# COBConnector.net
KiCad netlist of a schematic drawn in Altium Designer
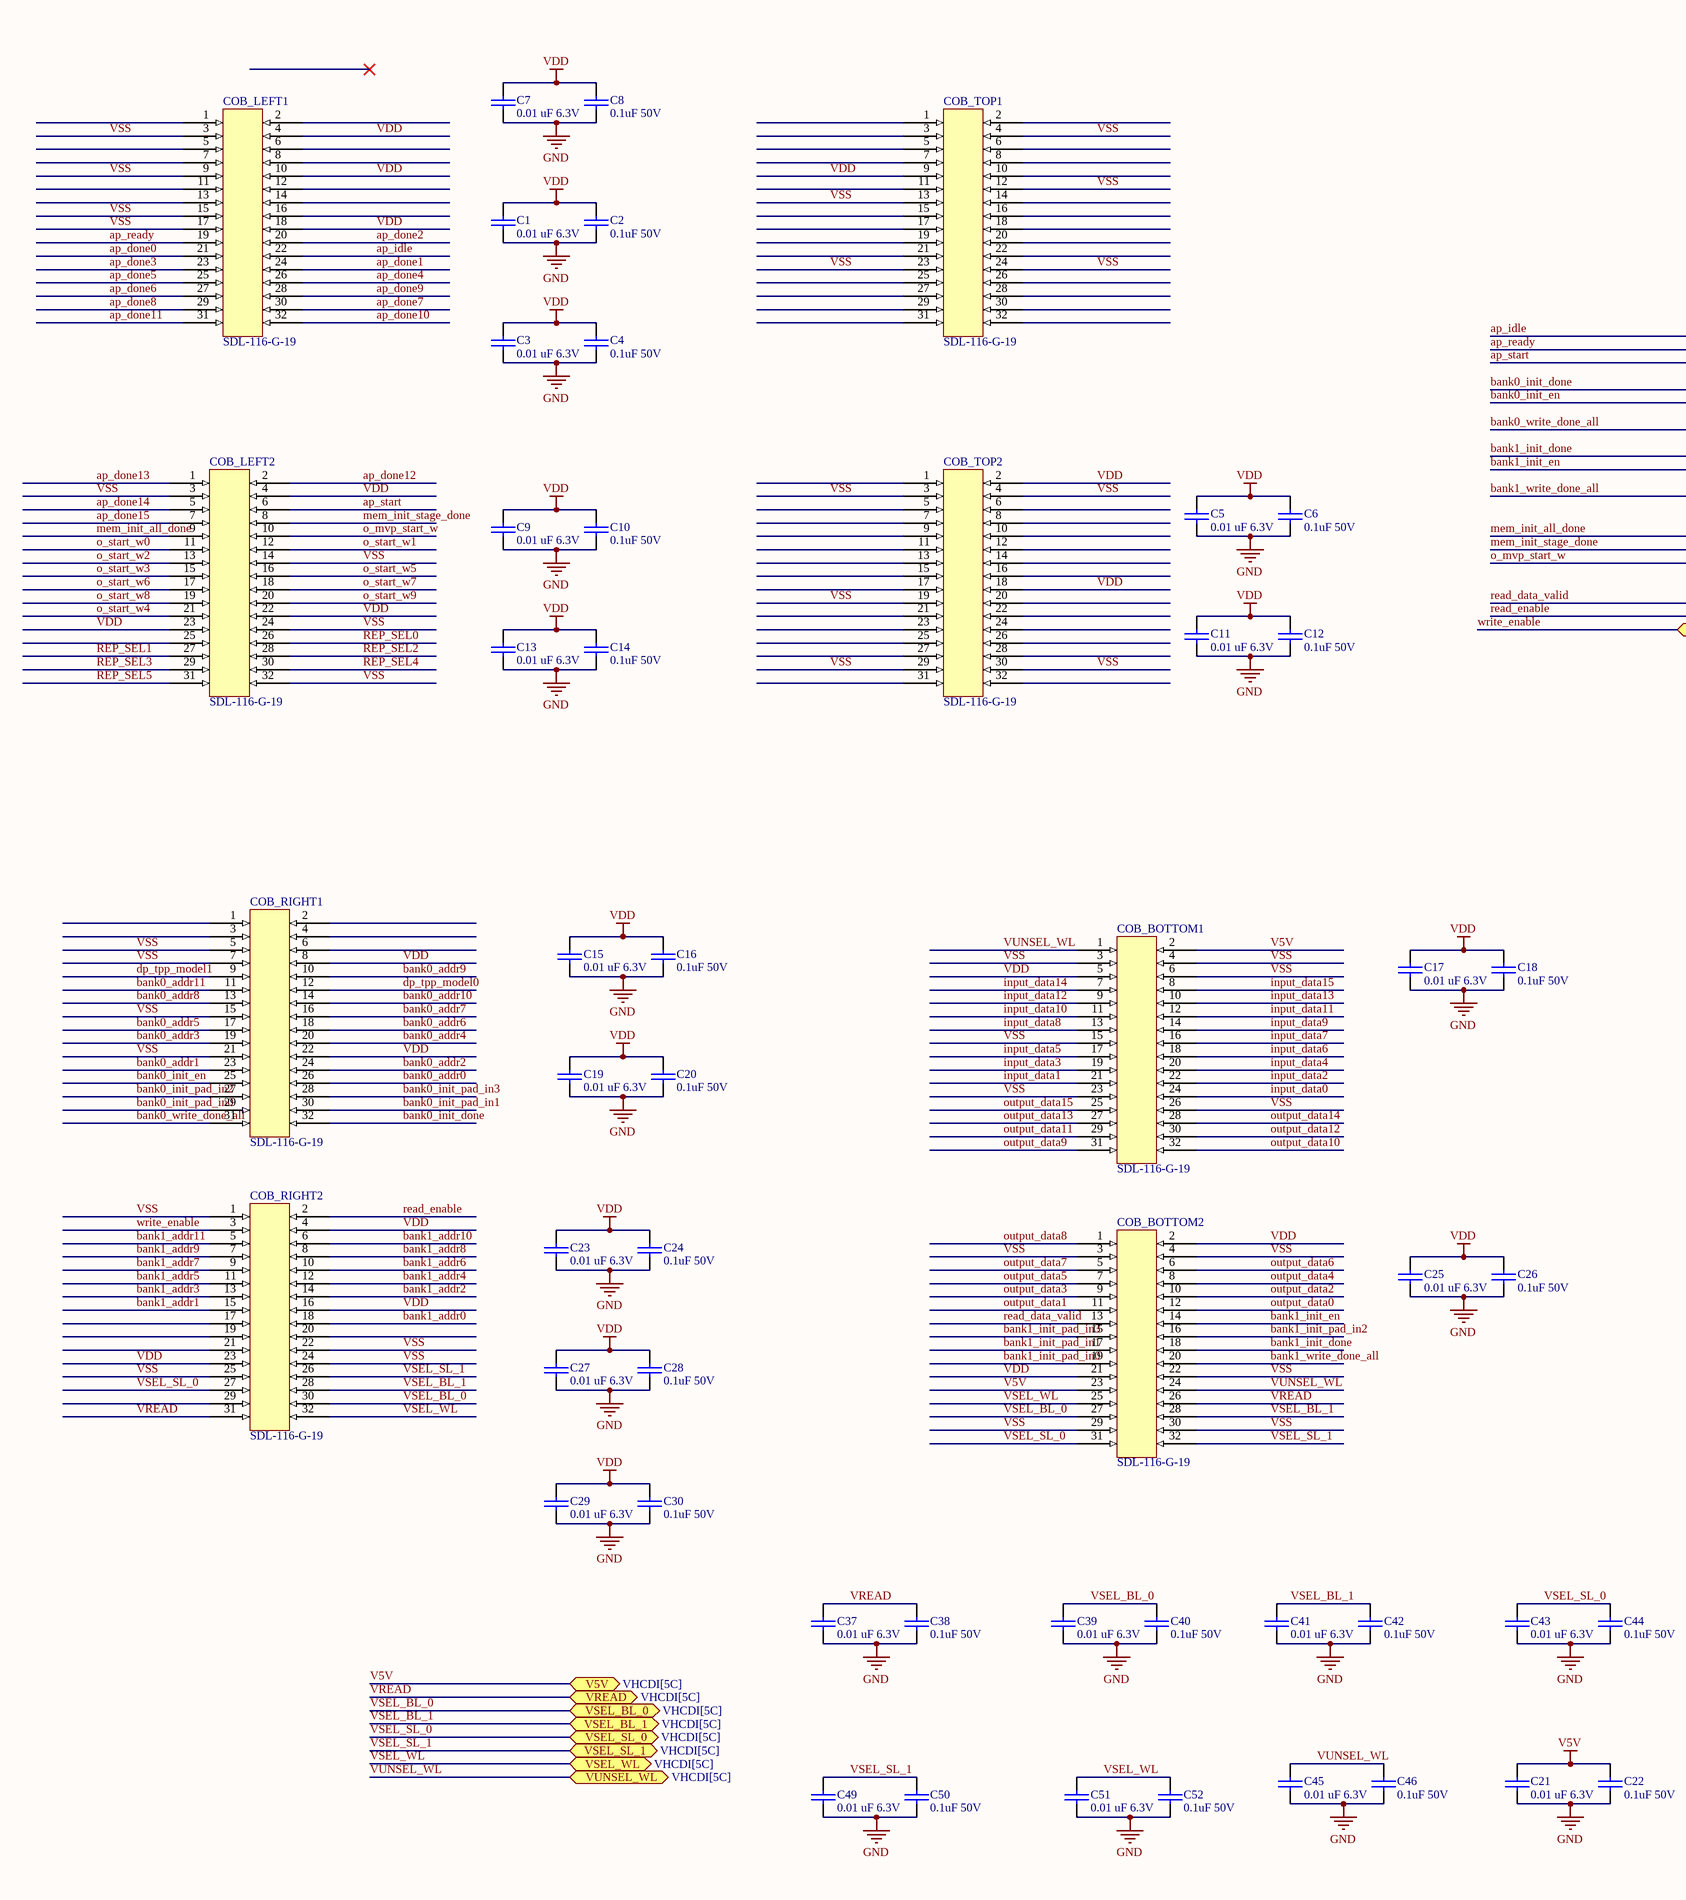
[diagram p0: COBConnector.SchDoc, left]
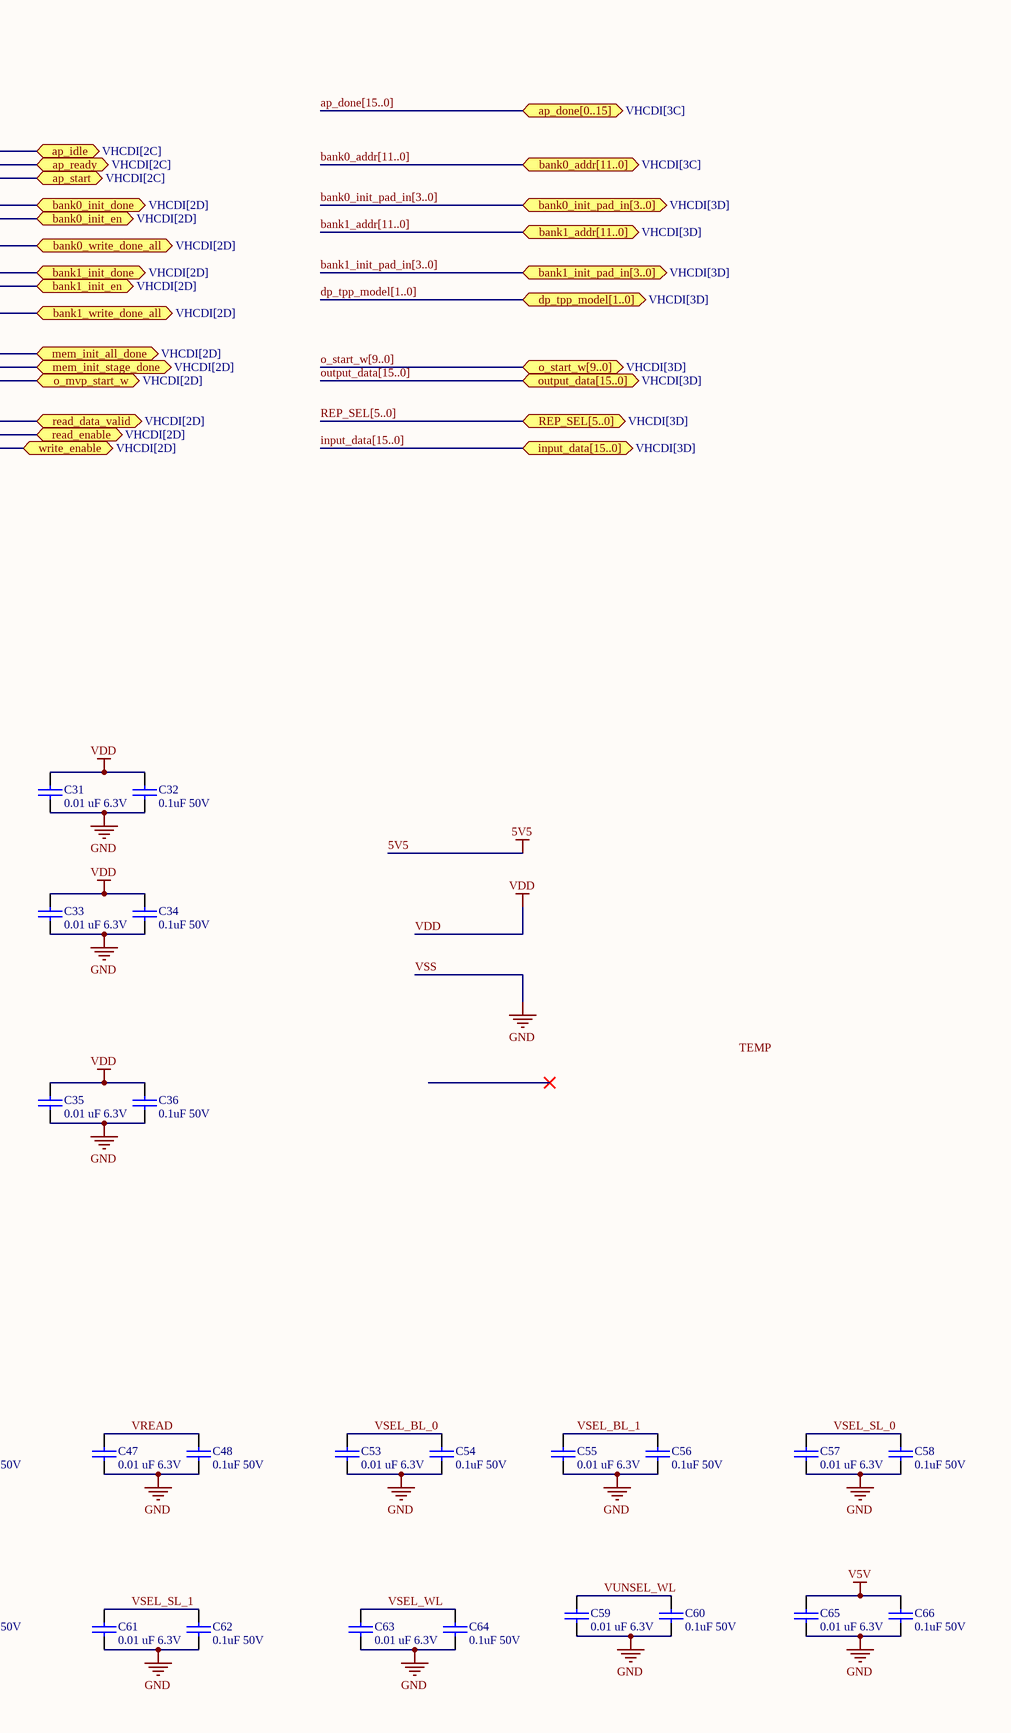
[diagram p1: COBConnector.SchDoc, right]

(export (version "E")
  (design (tool "Eeschema 10.0.6"))
  (components
    (comp (ref "C1")
      (value "0.01 uF 6.3V")
      (footprint "C0603-XXXXXX-XXX")
      (description "Multilayer Ceramic Capacitors MLCC - SMD/SMT 6.3V 0.01uF X7R 0603 20%")
      (libsource (lib "00-100001-001") (part "C0603F103M9RACTU"))
    )
    (comp (ref "C2")
      (value "0.1uF 50V")
      (footprint "C0603-XXXXXX-XXX")
      (description "0.1 µF ±20% 50V Ceramic Capacitor X7R 0603")
      (libsource (lib "00-100001-001") (part "C0603C104M5RAC7867"))
    )
    (comp (ref "C3")
      (value "0.01 uF 6.3V")
      (footprint "C0603-XXXXXX-XXX")
      (description "Multilayer Ceramic Capacitors MLCC - SMD/SMT 6.3V 0.01uF X7R 0603 20%")
      (libsource (lib "00-100001-001") (part "C0603F103M9RACTU"))
    )
    (comp (ref "C4")
      (value "0.1uF 50V")
      (footprint "C0603-XXXXXX-XXX")
      (description "0.1 µF ±20% 50V Ceramic Capacitor X7R 0603")
      (libsource (lib "00-100001-001") (part "C0603C104M5RAC7867"))
    )
    (comp (ref "C5")
      (value "0.01 uF 6.3V")
      (footprint "C0603-XXXXXX-XXX")
      (description "Multilayer Ceramic Capacitors MLCC - SMD/SMT 6.3V 0.01uF X7R 0603 20%")
      (libsource (lib "00-100001-001") (part "C0603F103M9RACTU"))
    )
    (comp (ref "C6")
      (value "0.1uF 50V")
      (footprint "C0603-XXXXXX-XXX")
      (description "0.1 µF ±20% 50V Ceramic Capacitor X7R 0603")
      (libsource (lib "00-100001-001") (part "C0603C104M5RAC7867"))
    )
    (comp (ref "C7")
      (value "0.01 uF 6.3V")
      (footprint "C0603-XXXXXX-XXX")
      (description "Multilayer Ceramic Capacitors MLCC - SMD/SMT 6.3V 0.01uF X7R 0603 20%")
      (libsource (lib "00-100001-001") (part "C0603F103M9RACTU"))
    )
    (comp (ref "C8")
      (value "0.1uF 50V")
      (footprint "C0603-XXXXXX-XXX")
      (description "0.1 µF ±20% 50V Ceramic Capacitor X7R 0603")
      (libsource (lib "00-100001-001") (part "C0603C104M5RAC7867"))
    )
    (comp (ref "C9")
      (value "0.01 uF 6.3V")
      (footprint "C0603-XXXXXX-XXX")
      (description "Multilayer Ceramic Capacitors MLCC - SMD/SMT 6.3V 0.01uF X7R 0603 20%")
      (libsource (lib "00-100001-001") (part "C0603F103M9RACTU"))
    )
    (comp (ref "C10")
      (value "0.1uF 50V")
      (footprint "C0603-XXXXXX-XXX")
      (description "0.1 µF ±20% 50V Ceramic Capacitor X7R 0603")
      (libsource (lib "00-100001-001") (part "C0603C104M5RAC7867"))
    )
    (comp (ref "C11")
      (value "0.01 uF 6.3V")
      (footprint "C0603-XXXXXX-XXX")
      (description "Multilayer Ceramic Capacitors MLCC - SMD/SMT 6.3V 0.01uF X7R 0603 20%")
      (libsource (lib "00-100001-001") (part "C0603F103M9RACTU"))
    )
    (comp (ref "C12")
      (value "0.1uF 50V")
      (footprint "C0603-XXXXXX-XXX")
      (description "0.1 µF ±20% 50V Ceramic Capacitor X7R 0603")
      (libsource (lib "00-100001-001") (part "C0603C104M5RAC7867"))
    )
    (comp (ref "C13")
      (value "0.01 uF 6.3V")
      (footprint "C0603-XXXXXX-XXX")
      (description "Multilayer Ceramic Capacitors MLCC - SMD/SMT 6.3V 0.01uF X7R 0603 20%")
      (libsource (lib "00-100001-001") (part "C0603F103M9RACTU"))
    )
    (comp (ref "C14")
      (value "0.1uF 50V")
      (footprint "C0603-XXXXXX-XXX")
      (description "0.1 µF ±20% 50V Ceramic Capacitor X7R 0603")
      (libsource (lib "00-100001-001") (part "C0603C104M5RAC7867"))
    )
    (comp (ref "C15")
      (value "0.01 uF 6.3V")
      (footprint "C0603-XXXXXX-XXX")
      (description "Multilayer Ceramic Capacitors MLCC - SMD/SMT 6.3V 0.01uF X7R 0603 20%")
      (libsource (lib "00-100001-001") (part "C0603F103M9RACTU"))
    )
    (comp (ref "C16")
      (value "0.1uF 50V")
      (footprint "C0603-XXXXXX-XXX")
      (description "0.1 µF ±20% 50V Ceramic Capacitor X7R 0603")
      (libsource (lib "00-100001-001") (part "C0603C104M5RAC7867"))
    )
    (comp (ref "C17")
      (value "0.01 uF 6.3V")
      (footprint "C0603-XXXXXX-XXX")
      (description "Multilayer Ceramic Capacitors MLCC - SMD/SMT 6.3V 0.01uF X7R 0603 20%")
      (libsource (lib "00-100001-001") (part "C0603F103M9RACTU"))
    )
    (comp (ref "C18")
      (value "0.1uF 50V")
      (footprint "C0603-XXXXXX-XXX")
      (description "0.1 µF ±20% 50V Ceramic Capacitor X7R 0603")
      (libsource (lib "00-100001-001") (part "C0603C104M5RAC7867"))
    )
    (comp (ref "C19")
      (value "0.01 uF 6.3V")
      (footprint "C0603-XXXXXX-XXX")
      (description "Multilayer Ceramic Capacitors MLCC - SMD/SMT 6.3V 0.01uF X7R 0603 20%")
      (libsource (lib "00-100001-001") (part "C0603F103M9RACTU"))
    )
    (comp (ref "C20")
      (value "0.1uF 50V")
      (footprint "C0603-XXXXXX-XXX")
      (description "0.1 µF ±20% 50V Ceramic Capacitor X7R 0603")
      (libsource (lib "00-100001-001") (part "C0603C104M5RAC7867"))
    )
    (comp (ref "C21")
      (value "0.01 uF 6.3V")
      (footprint "C0603-XXXXXX-XXX")
      (description "Multilayer Ceramic Capacitors MLCC - SMD/SMT 6.3V 0.01uF X7R 0603 20%")
      (libsource (lib "00-100001-001") (part "C0603F103M9RACTU"))
    )
    (comp (ref "C22")
      (value "0.1uF 50V")
      (footprint "C0603-XXXXXX-XXX")
      (description "0.1 µF ±20% 50V Ceramic Capacitor X7R 0603")
      (libsource (lib "00-100001-001") (part "C0603C104M5RAC7867"))
    )
    (comp (ref "C23")
      (value "0.01 uF 6.3V")
      (footprint "C0603-XXXXXX-XXX")
      (description "Multilayer Ceramic Capacitors MLCC - SMD/SMT 6.3V 0.01uF X7R 0603 20%")
      (libsource (lib "00-100001-001") (part "C0603F103M9RACTU"))
    )
    (comp (ref "C24")
      (value "0.1uF 50V")
      (footprint "C0603-XXXXXX-XXX")
      (description "0.1 µF ±20% 50V Ceramic Capacitor X7R 0603")
      (libsource (lib "00-100001-001") (part "C0603C104M5RAC7867"))
    )
    (comp (ref "C25")
      (value "0.01 uF 6.3V")
      (footprint "C0603-XXXXXX-XXX")
      (description "Multilayer Ceramic Capacitors MLCC - SMD/SMT 6.3V 0.01uF X7R 0603 20%")
      (libsource (lib "00-100001-001") (part "C0603F103M9RACTU"))
    )
    (comp (ref "C26")
      (value "0.1uF 50V")
      (footprint "C0603-XXXXXX-XXX")
      (description "0.1 µF ±20% 50V Ceramic Capacitor X7R 0603")
      (libsource (lib "00-100001-001") (part "C0603C104M5RAC7867"))
    )
    (comp (ref "C27")
      (value "0.01 uF 6.3V")
      (footprint "C0603-XXXXXX-XXX")
      (description "Multilayer Ceramic Capacitors MLCC - SMD/SMT 6.3V 0.01uF X7R 0603 20%")
      (libsource (lib "00-100001-001") (part "C0603F103M9RACTU"))
    )
    (comp (ref "C28")
      (value "0.1uF 50V")
      (footprint "C0603-XXXXXX-XXX")
      (description "0.1 µF ±20% 50V Ceramic Capacitor X7R 0603")
      (libsource (lib "00-100001-001") (part "C0603C104M5RAC7867"))
    )
    (comp (ref "C29")
      (value "0.01 uF 6.3V")
      (footprint "C0603-XXXXXX-XXX")
      (description "Multilayer Ceramic Capacitors MLCC - SMD/SMT 6.3V 0.01uF X7R 0603 20%")
      (libsource (lib "00-100001-001") (part "C0603F103M9RACTU"))
    )
    (comp (ref "C30")
      (value "0.1uF 50V")
      (footprint "C0603-XXXXXX-XXX")
      (description "0.1 µF ±20% 50V Ceramic Capacitor X7R 0603")
      (libsource (lib "00-100001-001") (part "C0603C104M5RAC7867"))
    )
    (comp (ref "C31")
      (value "0.01 uF 6.3V")
      (footprint "C0603-XXXXXX-XXX")
      (description "Multilayer Ceramic Capacitors MLCC - SMD/SMT 6.3V 0.01uF X7R 0603 20%")
      (libsource (lib "00-100001-001") (part "C0603F103M9RACTU"))
    )
    (comp (ref "C32")
      (value "0.1uF 50V")
      (footprint "C0603-XXXXXX-XXX")
      (description "0.1 µF ±20% 50V Ceramic Capacitor X7R 0603")
      (libsource (lib "00-100001-001") (part "C0603C104M5RAC7867"))
    )
    (comp (ref "C33")
      (value "0.01 uF 6.3V")
      (footprint "C0603-XXXXXX-XXX")
      (description "Multilayer Ceramic Capacitors MLCC - SMD/SMT 6.3V 0.01uF X7R 0603 20%")
      (libsource (lib "00-100001-001") (part "C0603F103M9RACTU"))
    )
    (comp (ref "C34")
      (value "0.1uF 50V")
      (footprint "C0603-XXXXXX-XXX")
      (description "0.1 µF ±20% 50V Ceramic Capacitor X7R 0603")
      (libsource (lib "00-100001-001") (part "C0603C104M5RAC7867"))
    )
    (comp (ref "C35")
      (value "0.01 uF 6.3V")
      (footprint "C0603-XXXXXX-XXX")
      (description "Multilayer Ceramic Capacitors MLCC - SMD/SMT 6.3V 0.01uF X7R 0603 20%")
      (libsource (lib "00-100001-001") (part "C0603F103M9RACTU"))
    )
    (comp (ref "C36")
      (value "0.1uF 50V")
      (footprint "C0603-XXXXXX-XXX")
      (description "0.1 µF ±20% 50V Ceramic Capacitor X7R 0603")
      (libsource (lib "00-100001-001") (part "C0603C104M5RAC7867"))
    )
    (comp (ref "C37")
      (value "0.01 uF 6.3V")
      (footprint "C0603-XXXXXX-XXX")
      (description "Multilayer Ceramic Capacitors MLCC - SMD/SMT 6.3V 0.01uF X7R 0603 20%")
      (libsource (lib "00-100001-001") (part "C0603F103M9RACTU"))
    )
    (comp (ref "C38")
      (value "0.1uF 50V")
      (footprint "C0603-XXXXXX-XXX")
      (description "0.1 µF ±20% 50V Ceramic Capacitor X7R 0603")
      (libsource (lib "00-100001-001") (part "C0603C104M5RAC7867"))
    )
    (comp (ref "C39")
      (value "0.01 uF 6.3V")
      (footprint "C0603-XXXXXX-XXX")
      (description "Multilayer Ceramic Capacitors MLCC - SMD/SMT 6.3V 0.01uF X7R 0603 20%")
      (libsource (lib "00-100001-001") (part "C0603F103M9RACTU"))
    )
    (comp (ref "C40")
      (value "0.1uF 50V")
      (footprint "C0603-XXXXXX-XXX")
      (description "0.1 µF ±20% 50V Ceramic Capacitor X7R 0603")
      (libsource (lib "00-100001-001") (part "C0603C104M5RAC7867"))
    )
    (comp (ref "C41")
      (value "0.01 uF 6.3V")
      (footprint "C0603-XXXXXX-XXX")
      (description "Multilayer Ceramic Capacitors MLCC - SMD/SMT 6.3V 0.01uF X7R 0603 20%")
      (libsource (lib "00-100001-001") (part "C0603F103M9RACTU"))
    )
    (comp (ref "C42")
      (value "0.1uF 50V")
      (footprint "C0603-XXXXXX-XXX")
      (description "0.1 µF ±20% 50V Ceramic Capacitor X7R 0603")
      (libsource (lib "00-100001-001") (part "C0603C104M5RAC7867"))
    )
    (comp (ref "C43")
      (value "0.01 uF 6.3V")
      (footprint "C0603-XXXXXX-XXX")
      (description "Multilayer Ceramic Capacitors MLCC - SMD/SMT 6.3V 0.01uF X7R 0603 20%")
      (libsource (lib "00-100001-001") (part "C0603F103M9RACTU"))
    )
    (comp (ref "C44")
      (value "0.1uF 50V")
      (footprint "C0603-XXXXXX-XXX")
      (description "0.1 µF ±20% 50V Ceramic Capacitor X7R 0603")
      (libsource (lib "00-100001-001") (part "C0603C104M5RAC7867"))
    )
    (comp (ref "C45")
      (value "0.01 uF 6.3V")
      (footprint "C0603-XXXXXX-XXX")
      (description "Multilayer Ceramic Capacitors MLCC - SMD/SMT 6.3V 0.01uF X7R 0603 20%")
      (libsource (lib "00-100001-001") (part "C0603F103M9RACTU"))
    )
    (comp (ref "C46")
      (value "0.1uF 50V")
      (footprint "C0603-XXXXXX-XXX")
      (description "0.1 µF ±20% 50V Ceramic Capacitor X7R 0603")
      (libsource (lib "00-100001-001") (part "C0603C104M5RAC7867"))
    )
    (comp (ref "C47")
      (value "0.01 uF 6.3V")
      (footprint "C0603-XXXXXX-XXX")
      (description "Multilayer Ceramic Capacitors MLCC - SMD/SMT 6.3V 0.01uF X7R 0603 20%")
      (libsource (lib "00-100001-001") (part "C0603F103M9RACTU"))
    )
    (comp (ref "C48")
      (value "0.1uF 50V")
      (footprint "C0603-XXXXXX-XXX")
      (description "0.1 µF ±20% 50V Ceramic Capacitor X7R 0603")
      (libsource (lib "00-100001-001") (part "C0603C104M5RAC7867"))
    )
    (comp (ref "C49")
      (value "0.01 uF 6.3V")
      (footprint "C0603-XXXXXX-XXX")
      (description "Multilayer Ceramic Capacitors MLCC - SMD/SMT 6.3V 0.01uF X7R 0603 20%")
      (libsource (lib "00-100001-001") (part "C0603F103M9RACTU"))
    )
    (comp (ref "C50")
      (value "0.1uF 50V")
      (footprint "C0603-XXXXXX-XXX")
      (description "0.1 µF ±20% 50V Ceramic Capacitor X7R 0603")
      (libsource (lib "00-100001-001") (part "C0603C104M5RAC7867"))
    )
    (comp (ref "C51")
      (value "0.01 uF 6.3V")
      (footprint "C0603-XXXXXX-XXX")
      (description "Multilayer Ceramic Capacitors MLCC - SMD/SMT 6.3V 0.01uF X7R 0603 20%")
      (libsource (lib "00-100001-001") (part "C0603F103M9RACTU"))
    )
    (comp (ref "C52")
      (value "0.1uF 50V")
      (footprint "C0603-XXXXXX-XXX")
      (description "0.1 µF ±20% 50V Ceramic Capacitor X7R 0603")
      (libsource (lib "00-100001-001") (part "C0603C104M5RAC7867"))
    )
    (comp (ref "C53")
      (value "0.01 uF 6.3V")
      (footprint "C0603-XXXXXX-XXX")
      (description "Multilayer Ceramic Capacitors MLCC - SMD/SMT 6.3V 0.01uF X7R 0603 20%")
      (libsource (lib "00-100001-001") (part "C0603F103M9RACTU"))
    )
    (comp (ref "C54")
      (value "0.1uF 50V")
      (footprint "C0603-XXXXXX-XXX")
      (description "0.1 µF ±20% 50V Ceramic Capacitor X7R 0603")
      (libsource (lib "00-100001-001") (part "C0603C104M5RAC7867"))
    )
    (comp (ref "C55")
      (value "0.01 uF 6.3V")
      (footprint "C0603-XXXXXX-XXX")
      (description "Multilayer Ceramic Capacitors MLCC - SMD/SMT 6.3V 0.01uF X7R 0603 20%")
      (libsource (lib "00-100001-001") (part "C0603F103M9RACTU"))
    )
    (comp (ref "C56")
      (value "0.1uF 50V")
      (footprint "C0603-XXXXXX-XXX")
      (description "0.1 µF ±20% 50V Ceramic Capacitor X7R 0603")
      (libsource (lib "00-100001-001") (part "C0603C104M5RAC7867"))
    )
    (comp (ref "C57")
      (value "0.01 uF 6.3V")
      (footprint "C0603-XXXXXX-XXX")
      (description "Multilayer Ceramic Capacitors MLCC - SMD/SMT 6.3V 0.01uF X7R 0603 20%")
      (libsource (lib "00-100001-001") (part "C0603F103M9RACTU"))
    )
    (comp (ref "C58")
      (value "0.1uF 50V")
      (footprint "C0603-XXXXXX-XXX")
      (description "0.1 µF ±20% 50V Ceramic Capacitor X7R 0603")
      (libsource (lib "00-100001-001") (part "C0603C104M5RAC7867"))
    )
    (comp (ref "C59")
      (value "0.01 uF 6.3V")
      (footprint "C0603-XXXXXX-XXX")
      (description "Multilayer Ceramic Capacitors MLCC - SMD/SMT 6.3V 0.01uF X7R 0603 20%")
      (libsource (lib "00-100001-001") (part "C0603F103M9RACTU"))
    )
    (comp (ref "C60")
      (value "0.1uF 50V")
      (footprint "C0603-XXXXXX-XXX")
      (description "0.1 µF ±20% 50V Ceramic Capacitor X7R 0603")
      (libsource (lib "00-100001-001") (part "C0603C104M5RAC7867"))
    )
    (comp (ref "C61")
      (value "0.01 uF 6.3V")
      (footprint "C0603-XXXXXX-XXX")
      (description "Multilayer Ceramic Capacitors MLCC - SMD/SMT 6.3V 0.01uF X7R 0603 20%")
      (libsource (lib "00-100001-001") (part "C0603F103M9RACTU"))
    )
    (comp (ref "C62")
      (value "0.1uF 50V")
      (footprint "C0603-XXXXXX-XXX")
      (description "0.1 µF ±20% 50V Ceramic Capacitor X7R 0603")
      (libsource (lib "00-100001-001") (part "C0603C104M5RAC7867"))
    )
    (comp (ref "C63")
      (value "0.01 uF 6.3V")
      (footprint "C0603-XXXXXX-XXX")
      (description "Multilayer Ceramic Capacitors MLCC - SMD/SMT 6.3V 0.01uF X7R 0603 20%")
      (libsource (lib "00-100001-001") (part "C0603F103M9RACTU"))
    )
    (comp (ref "C64")
      (value "0.1uF 50V")
      (footprint "C0603-XXXXXX-XXX")
      (description "0.1 µF ±20% 50V Ceramic Capacitor X7R 0603")
      (libsource (lib "00-100001-001") (part "C0603C104M5RAC7867"))
    )
    (comp (ref "C65")
      (value "0.01 uF 6.3V")
      (footprint "C0603-XXXXXX-XXX")
      (description "Multilayer Ceramic Capacitors MLCC - SMD/SMT 6.3V 0.01uF X7R 0603 20%")
      (libsource (lib "00-100001-001") (part "C0603F103M9RACTU"))
    )
    (comp (ref "C66")
      (value "0.1uF 50V")
      (footprint "C0603-XXXXXX-XXX")
      (description "0.1 µF ±20% 50V Ceramic Capacitor X7R 0603")
      (libsource (lib "00-100001-001") (part "C0603C104M5RAC7867"))
    )
    (comp (ref "COB_BOTTOM1")
      (value "SDL-116-G-19")
      (footprint "CON32_2X16_TU_DSL_SAI")
      (libsource (lib "00-100001-001") (part "SDL-116-G-19"))
    )
    (comp (ref "COB_BOTTOM2")
      (value "SDL-116-G-19")
      (footprint "CON32_2X16_TU_DSL_SAI")
      (libsource (lib "00-100001-001") (part "SDL-116-G-19"))
    )
    (comp (ref "COB_LEFT1")
      (value "SDL-116-G-19")
      (footprint "CON32_2X16_TU_DSL_SAI")
      (libsource (lib "00-100001-001") (part "SDL-116-G-19"))
    )
    (comp (ref "COB_LEFT2")
      (value "SDL-116-G-19")
      (footprint "CON32_2X16_TU_DSL_SAI")
      (libsource (lib "00-100001-001") (part "SDL-116-G-19"))
    )
    (comp (ref "COB_RIGHT1")
      (value "SDL-116-G-19")
      (footprint "CON32_2X16_TU_DSL_SAI")
      (libsource (lib "00-100001-001") (part "SDL-116-G-19"))
    )
    (comp (ref "COB_RIGHT2")
      (value "SDL-116-G-19")
      (footprint "CON32_2X16_TU_DSL_SAI")
      (libsource (lib "00-100001-001") (part "SDL-116-G-19"))
    )
    (comp (ref "COB_TOP1")
      (value "SDL-116-G-19")
      (footprint "CON32_2X16_TU_DSL_SAI")
      (libsource (lib "00-100001-001") (part "SDL-116-G-19"))
    )
    (comp (ref "COB_TOP2")
      (value "SDL-116-G-19")
      (footprint "CON32_2X16_TU_DSL_SAI")
      (libsource (lib "00-100001-001") (part "SDL-116-G-19"))
    )
  )
  (nets
    (net (code "1") (name "/REP_SEL0") (class "Default")
      (node (ref "COB_LEFT2") (pin "26") (pintype "input"))
    )
    (net (code "2") (name "/REP_SEL1") (class "Default")
      (node (ref "COB_LEFT2") (pin "27") (pintype "input"))
    )
    (net (code "3") (name "/REP_SEL2") (class "Default")
      (node (ref "COB_LEFT2") (pin "28") (pintype "input"))
    )
    (net (code "4") (name "/REP_SEL3") (class "Default")
      (node (ref "COB_LEFT2") (pin "29") (pintype "input"))
    )
    (net (code "5") (name "/REP_SEL4") (class "Default")
      (node (ref "COB_LEFT2") (pin "30") (pintype "input"))
    )
    (net (code "6") (name "/REP_SEL5") (class "Default")
      (node (ref "COB_LEFT2") (pin "31") (pintype "input"))
    )
    (net (code "9") (name "/VREAD") (class "Default")
      (node (ref "C37") (pin "1") (pinfunction "1_1") (pintype "passive"))
      (node (ref "C38") (pin "1") (pinfunction "1_1") (pintype "passive"))
      (node (ref "C47") (pin "1") (pinfunction "1_1") (pintype "passive"))
      (node (ref "C48") (pin "1") (pinfunction "1_1") (pintype "passive"))
      (node (ref "COB_BOTTOM2") (pin "26") (pintype "input"))
      (node (ref "COB_RIGHT2") (pin "31") (pintype "input"))
    )
    (net (code "10") (name "/VSEL_BL_0") (class "Default")
      (node (ref "C39") (pin "1") (pinfunction "1_1") (pintype "passive"))
      (node (ref "C40") (pin "1") (pinfunction "1_1") (pintype "passive"))
      (node (ref "C53") (pin "1") (pinfunction "1_1") (pintype "passive"))
      (node (ref "C54") (pin "1") (pinfunction "1_1") (pintype "passive"))
      (node (ref "COB_BOTTOM2") (pin "27") (pintype "input"))
      (node (ref "COB_RIGHT2") (pin "30") (pintype "input"))
    )
    (net (code "11") (name "/VSEL_BL_1") (class "Default")
      (node (ref "C41") (pin "1") (pinfunction "1_1") (pintype "passive"))
      (node (ref "C42") (pin "1") (pinfunction "1_1") (pintype "passive"))
      (node (ref "C55") (pin "1") (pinfunction "1_1") (pintype "passive"))
      (node (ref "C56") (pin "1") (pinfunction "1_1") (pintype "passive"))
      (node (ref "COB_BOTTOM2") (pin "28") (pintype "input"))
      (node (ref "COB_RIGHT2") (pin "28") (pintype "input"))
    )
    (net (code "12") (name "/VSEL_SL_0") (class "Default")
      (node (ref "C43") (pin "1") (pinfunction "1_1") (pintype "passive"))
      (node (ref "C44") (pin "1") (pinfunction "1_1") (pintype "passive"))
      (node (ref "C57") (pin "1") (pinfunction "1_1") (pintype "passive"))
      (node (ref "C58") (pin "1") (pinfunction "1_1") (pintype "passive"))
      (node (ref "COB_BOTTOM2") (pin "31") (pintype "input"))
      (node (ref "COB_RIGHT2") (pin "27") (pintype "input"))
    )
    (net (code "13") (name "/VSEL_SL_1") (class "Default")
      (node (ref "C49") (pin "1") (pinfunction "1_1") (pintype "passive"))
      (node (ref "C50") (pin "1") (pinfunction "1_1") (pintype "passive"))
      (node (ref "C61") (pin "1") (pinfunction "1_1") (pintype "passive"))
      (node (ref "C62") (pin "1") (pinfunction "1_1") (pintype "passive"))
      (node (ref "COB_BOTTOM2") (pin "32") (pintype "input"))
      (node (ref "COB_RIGHT2") (pin "26") (pintype "input"))
    )
    (net (code "14") (name "/VSEL_WL") (class "Default")
      (node (ref "C51") (pin "1") (pinfunction "1_1") (pintype "passive"))
      (node (ref "C52") (pin "1") (pinfunction "1_1") (pintype "passive"))
      (node (ref "C63") (pin "1") (pinfunction "1_1") (pintype "passive"))
      (node (ref "C64") (pin "1") (pinfunction "1_1") (pintype "passive"))
      (node (ref "COB_BOTTOM2") (pin "25") (pintype "input"))
      (node (ref "COB_RIGHT2") (pin "32") (pintype "input"))
    )
    (net (code "15") (name "/VUNSEL_WL") (class "Default")
      (node (ref "C45") (pin "1") (pinfunction "1_1") (pintype "passive"))
      (node (ref "C46") (pin "1") (pinfunction "1_1") (pintype "passive"))
      (node (ref "C59") (pin "1") (pinfunction "1_1") (pintype "passive"))
      (node (ref "C60") (pin "1") (pinfunction "1_1") (pintype "passive"))
      (node (ref "COB_BOTTOM1") (pin "1") (pintype "input"))
      (node (ref "COB_BOTTOM2") (pin "24") (pintype "input"))
    )
    (net (code "16") (name "/ap_done0") (class "Default")
      (node (ref "COB_LEFT1") (pin "21") (pintype "input"))
    )
    (net (code "17") (name "/ap_done1") (class "Default")
      (node (ref "COB_LEFT1") (pin "24") (pintype "input"))
    )
    (net (code "18") (name "/ap_done2") (class "Default")
      (node (ref "COB_LEFT1") (pin "20") (pintype "input"))
    )
    (net (code "19") (name "/ap_done3") (class "Default")
      (node (ref "COB_LEFT1") (pin "23") (pintype "input"))
    )
    (net (code "20") (name "/ap_done4") (class "Default")
      (node (ref "COB_LEFT1") (pin "26") (pintype "input"))
    )
    (net (code "21") (name "/ap_done5") (class "Default")
      (node (ref "COB_LEFT1") (pin "25") (pintype "input"))
    )
    (net (code "22") (name "/ap_done6") (class "Default")
      (node (ref "COB_LEFT1") (pin "27") (pintype "input"))
    )
    (net (code "23") (name "/ap_done7") (class "Default")
      (node (ref "COB_LEFT1") (pin "30") (pintype "input"))
    )
    (net (code "24") (name "/ap_done8") (class "Default")
      (node (ref "COB_LEFT1") (pin "29") (pintype "input"))
    )
    (net (code "25") (name "/ap_done9") (class "Default")
      (node (ref "COB_LEFT1") (pin "28") (pintype "input"))
    )
    (net (code "26") (name "/ap_done10") (class "Default")
      (node (ref "COB_LEFT1") (pin "32") (pintype "input"))
    )
    (net (code "27") (name "/ap_done11") (class "Default")
      (node (ref "COB_LEFT1") (pin "31") (pintype "input"))
    )
    (net (code "28") (name "/ap_done12") (class "Default")
      (node (ref "COB_LEFT2") (pin "2") (pintype "input"))
    )
    (net (code "29") (name "/ap_done13") (class "Default")
      (node (ref "COB_LEFT2") (pin "1") (pintype "input"))
    )
    (net (code "30") (name "/ap_done14") (class "Default")
      (node (ref "COB_LEFT2") (pin "5") (pintype "input"))
    )
    (net (code "31") (name "/ap_done15") (class "Default")
      (node (ref "COB_LEFT2") (pin "7") (pintype "input"))
    )
    (net (code "33") (name "/ap_idle") (class "Default")
      (node (ref "COB_LEFT1") (pin "22") (pintype "input"))
    )
    (net (code "34") (name "/ap_ready") (class "Default")
      (node (ref "COB_LEFT1") (pin "19") (pintype "input"))
    )
    (net (code "35") (name "/ap_start") (class "Default")
      (node (ref "COB_LEFT2") (pin "6") (pintype "input"))
    )
    (net (code "36") (name "/bank0_addr0") (class "Default")
      (node (ref "COB_RIGHT1") (pin "26") (pintype "input"))
    )
    (net (code "37") (name "/bank0_addr1") (class "Default")
      (node (ref "COB_RIGHT1") (pin "23") (pintype "input"))
    )
    (net (code "38") (name "/bank0_addr2") (class "Default")
      (node (ref "COB_RIGHT1") (pin "24") (pintype "input"))
    )
    (net (code "39") (name "/bank0_addr3") (class "Default")
      (node (ref "COB_RIGHT1") (pin "19") (pintype "input"))
    )
    (net (code "40") (name "/bank0_addr4") (class "Default")
      (node (ref "COB_RIGHT1") (pin "20") (pintype "input"))
    )
    (net (code "41") (name "/bank0_addr5") (class "Default")
      (node (ref "COB_RIGHT1") (pin "17") (pintype "input"))
    )
    (net (code "42") (name "/bank0_addr6") (class "Default")
      (node (ref "COB_RIGHT1") (pin "18") (pintype "input"))
    )
    (net (code "43") (name "/bank0_addr7") (class "Default")
      (node (ref "COB_RIGHT1") (pin "16") (pintype "input"))
    )
    (net (code "44") (name "/bank0_addr8") (class "Default")
      (node (ref "COB_RIGHT1") (pin "13") (pintype "input"))
    )
    (net (code "45") (name "/bank0_addr9") (class "Default")
      (node (ref "COB_RIGHT1") (pin "10") (pintype "input"))
    )
    (net (code "46") (name "/bank0_addr10") (class "Default")
      (node (ref "COB_RIGHT1") (pin "14") (pintype "input"))
    )
    (net (code "47") (name "/bank0_addr11") (class "Default")
      (node (ref "COB_RIGHT1") (pin "11") (pintype "input"))
    )
    (net (code "49") (name "/bank0_init_done") (class "Default")
      (node (ref "COB_RIGHT1") (pin "32") (pintype "input"))
    )
    (net (code "50") (name "/bank0_init_en") (class "Default")
      (node (ref "COB_RIGHT1") (pin "25") (pintype "input"))
    )
    (net (code "51") (name "/bank0_init_pad_in0") (class "Default")
      (node (ref "COB_RIGHT1") (pin "29") (pintype "input"))
    )
    (net (code "52") (name "/bank0_init_pad_in1") (class "Default")
      (node (ref "COB_RIGHT1") (pin "30") (pintype "input"))
    )
    (net (code "53") (name "/bank0_init_pad_in2") (class "Default")
      (node (ref "COB_RIGHT1") (pin "27") (pintype "input"))
    )
    (net (code "54") (name "/bank0_init_pad_in3") (class "Default")
      (node (ref "COB_RIGHT1") (pin "28") (pintype "input"))
    )
    (net (code "56") (name "/bank0_write_done_all") (class "Default")
      (node (ref "COB_RIGHT1") (pin "31") (pintype "input"))
    )
    (net (code "57") (name "/bank1_addr0") (class "Default")
      (node (ref "COB_RIGHT2") (pin "18") (pintype "input"))
    )
    (net (code "58") (name "/bank1_addr1") (class "Default")
      (node (ref "COB_RIGHT2") (pin "15") (pintype "input"))
    )
    (net (code "59") (name "/bank1_addr2") (class "Default")
      (node (ref "COB_RIGHT2") (pin "14") (pintype "input"))
    )
    (net (code "60") (name "/bank1_addr3") (class "Default")
      (node (ref "COB_RIGHT2") (pin "13") (pintype "input"))
    )
    (net (code "61") (name "/bank1_addr4") (class "Default")
      (node (ref "COB_RIGHT2") (pin "12") (pintype "input"))
    )
    (net (code "62") (name "/bank1_addr5") (class "Default")
      (node (ref "COB_RIGHT2") (pin "11") (pintype "input"))
    )
    (net (code "63") (name "/bank1_addr6") (class "Default")
      (node (ref "COB_RIGHT2") (pin "10") (pintype "input"))
    )
    (net (code "64") (name "/bank1_addr7") (class "Default")
      (node (ref "COB_RIGHT2") (pin "9") (pintype "input"))
    )
    (net (code "65") (name "/bank1_addr8") (class "Default")
      (node (ref "COB_RIGHT2") (pin "8") (pintype "input"))
    )
    (net (code "66") (name "/bank1_addr9") (class "Default")
      (node (ref "COB_RIGHT2") (pin "7") (pintype "input"))
    )
    (net (code "67") (name "/bank1_addr10") (class "Default")
      (node (ref "COB_RIGHT2") (pin "6") (pintype "input"))
    )
    (net (code "68") (name "/bank1_addr11") (class "Default")
      (node (ref "COB_RIGHT2") (pin "5") (pintype "input"))
    )
    (net (code "70") (name "/bank1_init_done") (class "Default")
      (node (ref "COB_BOTTOM2") (pin "18") (pintype "input"))
    )
    (net (code "71") (name "/bank1_init_en") (class "Default")
      (node (ref "COB_BOTTOM2") (pin "14") (pintype "input"))
    )
    (net (code "72") (name "/bank1_init_pad_in0") (class "Default")
      (node (ref "COB_BOTTOM2") (pin "19") (pintype "input"))
    )
    (net (code "73") (name "/bank1_init_pad_in1") (class "Default")
      (node (ref "COB_BOTTOM2") (pin "17") (pintype "input"))
    )
    (net (code "74") (name "/bank1_init_pad_in2") (class "Default")
      (node (ref "COB_BOTTOM2") (pin "16") (pintype "input"))
    )
    (net (code "75") (name "/bank1_init_pad_in3") (class "Default")
      (node (ref "COB_BOTTOM2") (pin "15") (pintype "input"))
    )
    (net (code "77") (name "/bank1_write_done_all") (class "Default")
      (node (ref "COB_BOTTOM2") (pin "20") (pintype "input"))
    )
    (net (code "78") (name "/dp_tpp_model0") (class "Default")
      (node (ref "COB_RIGHT1") (pin "12") (pintype "input"))
    )
    (net (code "79") (name "/dp_tpp_model1") (class "Default")
      (node (ref "COB_RIGHT1") (pin "9") (pintype "input"))
    )
    (net (code "81") (name "/input_data0") (class "Default")
      (node (ref "COB_BOTTOM1") (pin "24") (pintype "input"))
    )
    (net (code "82") (name "/input_data1") (class "Default")
      (node (ref "COB_BOTTOM1") (pin "21") (pintype "input"))
    )
    (net (code "83") (name "/input_data2") (class "Default")
      (node (ref "COB_BOTTOM1") (pin "22") (pintype "input"))
    )
    (net (code "84") (name "/input_data3") (class "Default")
      (node (ref "COB_BOTTOM1") (pin "19") (pintype "input"))
    )
    (net (code "85") (name "/input_data4") (class "Default")
      (node (ref "COB_BOTTOM1") (pin "20") (pintype "input"))
    )
    (net (code "86") (name "/input_data5") (class "Default")
      (node (ref "COB_BOTTOM1") (pin "17") (pintype "input"))
    )
    (net (code "87") (name "/input_data6") (class "Default")
      (node (ref "COB_BOTTOM1") (pin "18") (pintype "input"))
    )
    (net (code "88") (name "/input_data7") (class "Default")
      (node (ref "COB_BOTTOM1") (pin "16") (pintype "input"))
    )
    (net (code "89") (name "/input_data8") (class "Default")
      (node (ref "COB_BOTTOM1") (pin "13") (pintype "input"))
    )
    (net (code "90") (name "/input_data9") (class "Default")
      (node (ref "COB_BOTTOM1") (pin "14") (pintype "input"))
    )
    (net (code "91") (name "/input_data10") (class "Default")
      (node (ref "COB_BOTTOM1") (pin "11") (pintype "input"))
    )
    (net (code "92") (name "/input_data11") (class "Default")
      (node (ref "COB_BOTTOM1") (pin "12") (pintype "input"))
    )
    (net (code "93") (name "/input_data12") (class "Default")
      (node (ref "COB_BOTTOM1") (pin "9") (pintype "input"))
    )
    (net (code "94") (name "/input_data13") (class "Default")
      (node (ref "COB_BOTTOM1") (pin "10") (pintype "input"))
    )
    (net (code "95") (name "/input_data14") (class "Default")
      (node (ref "COB_BOTTOM1") (pin "7") (pintype "input"))
    )
    (net (code "96") (name "/input_data15") (class "Default")
      (node (ref "COB_BOTTOM1") (pin "8") (pintype "input"))
    )
    (net (code "98") (name "/mem_init_all_done") (class "Default")
      (node (ref "COB_LEFT2") (pin "9") (pintype "input"))
    )
    (net (code "99") (name "/mem_init_stage_done") (class "Default")
      (node (ref "COB_LEFT2") (pin "8") (pintype "input"))
    )
    (net (code "100") (name "/o_mvp_start_w") (class "Default")
      (node (ref "COB_LEFT2") (pin "10") (pintype "input"))
    )
    (net (code "101") (name "/o_start_w0") (class "Default")
      (node (ref "COB_LEFT2") (pin "11") (pintype "input"))
    )
    (net (code "102") (name "/o_start_w1") (class "Default")
      (node (ref "COB_LEFT2") (pin "12") (pintype "input"))
    )
    (net (code "103") (name "/o_start_w2") (class "Default")
      (node (ref "COB_LEFT2") (pin "13") (pintype "input"))
    )
    (net (code "104") (name "/o_start_w3") (class "Default")
      (node (ref "COB_LEFT2") (pin "15") (pintype "input"))
    )
    (net (code "105") (name "/o_start_w4") (class "Default")
      (node (ref "COB_LEFT2") (pin "21") (pintype "input"))
    )
    (net (code "106") (name "/o_start_w5") (class "Default")
      (node (ref "COB_LEFT2") (pin "16") (pintype "input"))
    )
    (net (code "107") (name "/o_start_w6") (class "Default")
      (node (ref "COB_LEFT2") (pin "17") (pintype "input"))
    )
    (net (code "108") (name "/o_start_w7") (class "Default")
      (node (ref "COB_LEFT2") (pin "18") (pintype "input"))
    )
    (net (code "109") (name "/o_start_w8") (class "Default")
      (node (ref "COB_LEFT2") (pin "19") (pintype "input"))
    )
    (net (code "110") (name "/o_start_w9") (class "Default")
      (node (ref "COB_LEFT2") (pin "20") (pintype "input"))
    )
    (net (code "112") (name "/output_data0") (class "Default")
      (node (ref "COB_BOTTOM2") (pin "12") (pintype "input"))
    )
    (net (code "113") (name "/output_data1") (class "Default")
      (node (ref "COB_BOTTOM2") (pin "11") (pintype "input"))
    )
    (net (code "114") (name "/output_data2") (class "Default")
      (node (ref "COB_BOTTOM2") (pin "10") (pintype "input"))
    )
    (net (code "115") (name "/output_data3") (class "Default")
      (node (ref "COB_BOTTOM2") (pin "9") (pintype "input"))
    )
    (net (code "116") (name "/output_data4") (class "Default")
      (node (ref "COB_BOTTOM2") (pin "8") (pintype "input"))
    )
    (net (code "117") (name "/output_data5") (class "Default")
      (node (ref "COB_BOTTOM2") (pin "7") (pintype "input"))
    )
    (net (code "118") (name "/output_data6") (class "Default")
      (node (ref "COB_BOTTOM2") (pin "6") (pintype "input"))
    )
    (net (code "119") (name "/output_data7") (class "Default")
      (node (ref "COB_BOTTOM2") (pin "5") (pintype "input"))
    )
    (net (code "120") (name "/output_data8") (class "Default")
      (node (ref "COB_BOTTOM2") (pin "1") (pintype "input"))
    )
    (net (code "121") (name "/output_data9") (class "Default")
      (node (ref "COB_BOTTOM1") (pin "31") (pintype "input"))
    )
    (net (code "122") (name "/output_data10") (class "Default")
      (node (ref "COB_BOTTOM1") (pin "32") (pintype "input"))
    )
    (net (code "123") (name "/output_data11") (class "Default")
      (node (ref "COB_BOTTOM1") (pin "29") (pintype "input"))
    )
    (net (code "124") (name "/output_data12") (class "Default")
      (node (ref "COB_BOTTOM1") (pin "30") (pintype "input"))
    )
    (net (code "125") (name "/output_data13") (class "Default")
      (node (ref "COB_BOTTOM1") (pin "27") (pintype "input"))
    )
    (net (code "126") (name "/output_data14") (class "Default")
      (node (ref "COB_BOTTOM1") (pin "28") (pintype "input"))
    )
    (net (code "127") (name "/output_data15") (class "Default")
      (node (ref "COB_BOTTOM1") (pin "25") (pintype "input"))
    )
    (net (code "129") (name "/read_data_valid") (class "Default")
      (node (ref "COB_BOTTOM2") (pin "13") (pintype "input"))
    )
    (net (code "130") (name "/read_enable") (class "Default")
      (node (ref "COB_RIGHT2") (pin "2") (pintype "input"))
    )
    (net (code "131") (name "/write_enable") (class "Default")
      (node (ref "COB_RIGHT2") (pin "3") (pintype "input"))
    )
    (net (code "133") (name "GND") (class "Default")
      (node (ref "C1") (pin "2") (pinfunction "2_2") (pintype "passive"))
      (node (ref "C10") (pin "2") (pinfunction "2_2") (pintype "passive"))
      (node (ref "C11") (pin "2") (pinfunction "2_2") (pintype "passive"))
      (node (ref "C12") (pin "2") (pinfunction "2_2") (pintype "passive"))
      (node (ref "C13") (pin "2") (pinfunction "2_2") (pintype "passive"))
      (node (ref "C14") (pin "2") (pinfunction "2_2") (pintype "passive"))
      (node (ref "C15") (pin "2") (pinfunction "2_2") (pintype "passive"))
      (node (ref "C16") (pin "2") (pinfunction "2_2") (pintype "passive"))
      (node (ref "C17") (pin "2") (pinfunction "2_2") (pintype "passive"))
      (node (ref "C18") (pin "2") (pinfunction "2_2") (pintype "passive"))
      (node (ref "C19") (pin "2") (pinfunction "2_2") (pintype "passive"))
      (node (ref "C2") (pin "2") (pinfunction "2_2") (pintype "passive"))
      (node (ref "C20") (pin "2") (pinfunction "2_2") (pintype "passive"))
      (node (ref "C21") (pin "2") (pinfunction "2_2") (pintype "passive"))
      (node (ref "C22") (pin "2") (pinfunction "2_2") (pintype "passive"))
      (node (ref "C23") (pin "2") (pinfunction "2_2") (pintype "passive"))
      (node (ref "C24") (pin "2") (pinfunction "2_2") (pintype "passive"))
      (node (ref "C25") (pin "2") (pinfunction "2_2") (pintype "passive"))
      (node (ref "C26") (pin "2") (pinfunction "2_2") (pintype "passive"))
      (node (ref "C27") (pin "2") (pinfunction "2_2") (pintype "passive"))
      (node (ref "C28") (pin "2") (pinfunction "2_2") (pintype "passive"))
      (node (ref "C29") (pin "2") (pinfunction "2_2") (pintype "passive"))
      (node (ref "C3") (pin "2") (pinfunction "2_2") (pintype "passive"))
      (node (ref "C30") (pin "2") (pinfunction "2_2") (pintype "passive"))
      (node (ref "C31") (pin "2") (pinfunction "2_2") (pintype "passive"))
      (node (ref "C32") (pin "2") (pinfunction "2_2") (pintype "passive"))
      (node (ref "C33") (pin "2") (pinfunction "2_2") (pintype "passive"))
      (node (ref "C34") (pin "2") (pinfunction "2_2") (pintype "passive"))
      (node (ref "C35") (pin "2") (pinfunction "2_2") (pintype "passive"))
      (node (ref "C36") (pin "2") (pinfunction "2_2") (pintype "passive"))
      (node (ref "C37") (pin "2") (pinfunction "2_2") (pintype "passive"))
      (node (ref "C38") (pin "2") (pinfunction "2_2") (pintype "passive"))
      (node (ref "C39") (pin "2") (pinfunction "2_2") (pintype "passive"))
      (node (ref "C4") (pin "2") (pinfunction "2_2") (pintype "passive"))
      (node (ref "C40") (pin "2") (pinfunction "2_2") (pintype "passive"))
      (node (ref "C41") (pin "2") (pinfunction "2_2") (pintype "passive"))
      (node (ref "C42") (pin "2") (pinfunction "2_2") (pintype "passive"))
      (node (ref "C43") (pin "2") (pinfunction "2_2") (pintype "passive"))
      (node (ref "C44") (pin "2") (pinfunction "2_2") (pintype "passive"))
      (node (ref "C45") (pin "2") (pinfunction "2_2") (pintype "passive"))
      (node (ref "C46") (pin "2") (pinfunction "2_2") (pintype "passive"))
      (node (ref "C47") (pin "2") (pinfunction "2_2") (pintype "passive"))
      (node (ref "C48") (pin "2") (pinfunction "2_2") (pintype "passive"))
      (node (ref "C49") (pin "2") (pinfunction "2_2") (pintype "passive"))
      (node (ref "C5") (pin "2") (pinfunction "2_2") (pintype "passive"))
      (node (ref "C50") (pin "2") (pinfunction "2_2") (pintype "passive"))
      (node (ref "C51") (pin "2") (pinfunction "2_2") (pintype "passive"))
      (node (ref "C52") (pin "2") (pinfunction "2_2") (pintype "passive"))
      (node (ref "C53") (pin "2") (pinfunction "2_2") (pintype "passive"))
      (node (ref "C54") (pin "2") (pinfunction "2_2") (pintype "passive"))
      (node (ref "C55") (pin "2") (pinfunction "2_2") (pintype "passive"))
      (node (ref "C56") (pin "2") (pinfunction "2_2") (pintype "passive"))
      (node (ref "C57") (pin "2") (pinfunction "2_2") (pintype "passive"))
      (node (ref "C58") (pin "2") (pinfunction "2_2") (pintype "passive"))
      (node (ref "C59") (pin "2") (pinfunction "2_2") (pintype "passive"))
      (node (ref "C6") (pin "2") (pinfunction "2_2") (pintype "passive"))
      (node (ref "C60") (pin "2") (pinfunction "2_2") (pintype "passive"))
      (node (ref "C61") (pin "2") (pinfunction "2_2") (pintype "passive"))
      (node (ref "C62") (pin "2") (pinfunction "2_2") (pintype "passive"))
      (node (ref "C63") (pin "2") (pinfunction "2_2") (pintype "passive"))
      (node (ref "C64") (pin "2") (pinfunction "2_2") (pintype "passive"))
      (node (ref "C65") (pin "2") (pinfunction "2_2") (pintype "passive"))
      (node (ref "C66") (pin "2") (pinfunction "2_2") (pintype "passive"))
      (node (ref "C7") (pin "2") (pinfunction "2_2") (pintype "passive"))
      (node (ref "C8") (pin "2") (pinfunction "2_2") (pintype "passive"))
      (node (ref "C9") (pin "2") (pinfunction "2_2") (pintype "passive"))
      (node (ref "COB_BOTTOM1") (pin "15") (pintype "input"))
      (node (ref "COB_BOTTOM1") (pin "23") (pintype "input"))
      (node (ref "COB_BOTTOM1") (pin "26") (pintype "input"))
      (node (ref "COB_BOTTOM1") (pin "3") (pintype "input"))
      (node (ref "COB_BOTTOM1") (pin "4") (pintype "input"))
      (node (ref "COB_BOTTOM1") (pin "6") (pintype "input"))
      (node (ref "COB_BOTTOM2") (pin "22") (pintype "input"))
      (node (ref "COB_BOTTOM2") (pin "29") (pintype "input"))
      (node (ref "COB_BOTTOM2") (pin "3") (pintype "input"))
      (node (ref "COB_BOTTOM2") (pin "30") (pintype "input"))
      (node (ref "COB_BOTTOM2") (pin "4") (pintype "input"))
      (node (ref "COB_LEFT1") (pin "15") (pintype "input"))
      (node (ref "COB_LEFT1") (pin "17") (pintype "input"))
      (node (ref "COB_LEFT1") (pin "3") (pintype "input"))
      (node (ref "COB_LEFT1") (pin "9") (pintype "input"))
      (node (ref "COB_LEFT2") (pin "14") (pintype "input"))
      (node (ref "COB_LEFT2") (pin "24") (pintype "input"))
      (node (ref "COB_LEFT2") (pin "3") (pintype "input"))
      (node (ref "COB_LEFT2") (pin "32") (pintype "input"))
      (node (ref "COB_RIGHT1") (pin "15") (pintype "input"))
      (node (ref "COB_RIGHT1") (pin "21") (pintype "input"))
      (node (ref "COB_RIGHT1") (pin "5") (pintype "input"))
      (node (ref "COB_RIGHT1") (pin "7") (pintype "input"))
      (node (ref "COB_RIGHT2") (pin "1") (pintype "input"))
      (node (ref "COB_RIGHT2") (pin "22") (pintype "input"))
      (node (ref "COB_RIGHT2") (pin "24") (pintype "input"))
      (node (ref "COB_RIGHT2") (pin "25") (pintype "input"))
      (node (ref "COB_TOP1") (pin "12") (pintype "input"))
      (node (ref "COB_TOP1") (pin "13") (pintype "input"))
      (node (ref "COB_TOP1") (pin "23") (pintype "input"))
      (node (ref "COB_TOP1") (pin "24") (pintype "input"))
      (node (ref "COB_TOP1") (pin "4") (pintype "input"))
      (node (ref "COB_TOP2") (pin "19") (pintype "input"))
      (node (ref "COB_TOP2") (pin "29") (pintype "input"))
      (node (ref "COB_TOP2") (pin "3") (pintype "input"))
      (node (ref "COB_TOP2") (pin "30") (pintype "input"))
      (node (ref "COB_TOP2") (pin "4") (pintype "input"))
    )
    (net (code "134") (name "V5V") (class "Default")
      (node (ref "C21") (pin "1") (pinfunction "1_1") (pintype "passive"))
      (node (ref "C22") (pin "1") (pinfunction "1_1") (pintype "passive"))
      (node (ref "C65") (pin "1") (pinfunction "1_1") (pintype "passive"))
      (node (ref "C66") (pin "1") (pinfunction "1_1") (pintype "passive"))
      (node (ref "COB_BOTTOM1") (pin "2") (pintype "input"))
      (node (ref "COB_BOTTOM2") (pin "23") (pintype "input"))
    )
    (net (code "135") (name "VDD") (class "Default")
      (node (ref "C1") (pin "1") (pinfunction "1_1") (pintype "passive"))
      (node (ref "C10") (pin "1") (pinfunction "1_1") (pintype "passive"))
      (node (ref "C11") (pin "1") (pinfunction "1_1") (pintype "passive"))
      (node (ref "C12") (pin "1") (pinfunction "1_1") (pintype "passive"))
      (node (ref "C13") (pin "1") (pinfunction "1_1") (pintype "passive"))
      (node (ref "C14") (pin "1") (pinfunction "1_1") (pintype "passive"))
      (node (ref "C15") (pin "1") (pinfunction "1_1") (pintype "passive"))
      (node (ref "C16") (pin "1") (pinfunction "1_1") (pintype "passive"))
      (node (ref "C17") (pin "1") (pinfunction "1_1") (pintype "passive"))
      (node (ref "C18") (pin "1") (pinfunction "1_1") (pintype "passive"))
      (node (ref "C19") (pin "1") (pinfunction "1_1") (pintype "passive"))
      (node (ref "C2") (pin "1") (pinfunction "1_1") (pintype "passive"))
      (node (ref "C20") (pin "1") (pinfunction "1_1") (pintype "passive"))
      (node (ref "C23") (pin "1") (pinfunction "1_1") (pintype "passive"))
      (node (ref "C24") (pin "1") (pinfunction "1_1") (pintype "passive"))
      (node (ref "C25") (pin "1") (pinfunction "1_1") (pintype "passive"))
      (node (ref "C26") (pin "1") (pinfunction "1_1") (pintype "passive"))
      (node (ref "C27") (pin "1") (pinfunction "1_1") (pintype "passive"))
      (node (ref "C28") (pin "1") (pinfunction "1_1") (pintype "passive"))
      (node (ref "C29") (pin "1") (pinfunction "1_1") (pintype "passive"))
      (node (ref "C3") (pin "1") (pinfunction "1_1") (pintype "passive"))
      (node (ref "C30") (pin "1") (pinfunction "1_1") (pintype "passive"))
      (node (ref "C31") (pin "1") (pinfunction "1_1") (pintype "passive"))
      (node (ref "C32") (pin "1") (pinfunction "1_1") (pintype "passive"))
      (node (ref "C33") (pin "1") (pinfunction "1_1") (pintype "passive"))
      (node (ref "C34") (pin "1") (pinfunction "1_1") (pintype "passive"))
      (node (ref "C35") (pin "1") (pinfunction "1_1") (pintype "passive"))
      (node (ref "C36") (pin "1") (pinfunction "1_1") (pintype "passive"))
      (node (ref "C4") (pin "1") (pinfunction "1_1") (pintype "passive"))
      (node (ref "C5") (pin "1") (pinfunction "1_1") (pintype "passive"))
      (node (ref "C6") (pin "1") (pinfunction "1_1") (pintype "passive"))
      (node (ref "C7") (pin "1") (pinfunction "1_1") (pintype "passive"))
      (node (ref "C8") (pin "1") (pinfunction "1_1") (pintype "passive"))
      (node (ref "C9") (pin "1") (pinfunction "1_1") (pintype "passive"))
      (node (ref "COB_BOTTOM1") (pin "5") (pintype "input"))
      (node (ref "COB_BOTTOM2") (pin "2") (pintype "input"))
      (node (ref "COB_BOTTOM2") (pin "21") (pintype "input"))
      (node (ref "COB_LEFT1") (pin "10") (pintype "input"))
      (node (ref "COB_LEFT1") (pin "18") (pintype "input"))
      (node (ref "COB_LEFT1") (pin "4") (pintype "input"))
      (node (ref "COB_LEFT2") (pin "22") (pintype "input"))
      (node (ref "COB_LEFT2") (pin "23") (pintype "input"))
      (node (ref "COB_LEFT2") (pin "4") (pintype "input"))
      (node (ref "COB_RIGHT1") (pin "22") (pintype "input"))
      (node (ref "COB_RIGHT1") (pin "8") (pintype "input"))
      (node (ref "COB_RIGHT2") (pin "16") (pintype "input"))
      (node (ref "COB_RIGHT2") (pin "23") (pintype "input"))
      (node (ref "COB_RIGHT2") (pin "4") (pintype "input"))
      (node (ref "COB_TOP1") (pin "9") (pintype "input"))
      (node (ref "COB_TOP2") (pin "18") (pintype "input"))
      (node (ref "COB_TOP2") (pin "2") (pintype "input"))
    )
    (net (code "136") (name "unconnected-(COB_LEFT1-Pad1)") (class "Default")
      (node (ref "COB_LEFT1") (pin "1") (pintype "input"))
    )
    (net (code "137") (name "unconnected-(COB_LEFT1-Pad2)") (class "Default")
      (node (ref "COB_LEFT1") (pin "2") (pintype "input"))
    )
    (net (code "138") (name "unconnected-(COB_LEFT1-Pad5)") (class "Default")
      (node (ref "COB_LEFT1") (pin "5") (pintype "input"))
    )
    (net (code "139") (name "unconnected-(COB_LEFT1-Pad6)") (class "Default")
      (node (ref "COB_LEFT1") (pin "6") (pintype "input"))
    )
    (net (code "140") (name "unconnected-(COB_LEFT1-Pad7)") (class "Default")
      (node (ref "COB_LEFT1") (pin "7") (pintype "input"))
    )
    (net (code "141") (name "unconnected-(COB_LEFT1-Pad8)") (class "Default")
      (node (ref "COB_LEFT1") (pin "8") (pintype "input"))
    )
    (net (code "142") (name "unconnected-(COB_LEFT1-Pad11)") (class "Default")
      (node (ref "COB_LEFT1") (pin "11") (pintype "input"))
    )
    (net (code "143") (name "unconnected-(COB_LEFT1-Pad12)") (class "Default")
      (node (ref "COB_LEFT1") (pin "12") (pintype "input"))
    )
    (net (code "144") (name "unconnected-(COB_LEFT1-Pad13)") (class "Default")
      (node (ref "COB_LEFT1") (pin "13") (pintype "input"))
    )
    (net (code "145") (name "unconnected-(COB_LEFT1-Pad14)") (class "Default")
      (node (ref "COB_LEFT1") (pin "14") (pintype "input"))
    )
    (net (code "146") (name "unconnected-(COB_LEFT1-Pad16)") (class "Default")
      (node (ref "COB_LEFT1") (pin "16") (pintype "input"))
    )
    (net (code "147") (name "unconnected-(COB_LEFT2-Pad25)") (class "Default")
      (node (ref "COB_LEFT2") (pin "25") (pintype "input"))
    )
    (net (code "148") (name "unconnected-(COB_RIGHT1-Pad1)") (class "Default")
      (node (ref "COB_RIGHT1") (pin "1") (pintype "input"))
    )
    (net (code "149") (name "unconnected-(COB_RIGHT1-Pad2)") (class "Default")
      (node (ref "COB_RIGHT1") (pin "2") (pintype "input"))
    )
    (net (code "150") (name "unconnected-(COB_RIGHT1-Pad3)") (class "Default")
      (node (ref "COB_RIGHT1") (pin "3") (pintype "input"))
    )
    (net (code "151") (name "unconnected-(COB_RIGHT1-Pad4)") (class "Default")
      (node (ref "COB_RIGHT1") (pin "4") (pintype "input"))
    )
    (net (code "152") (name "unconnected-(COB_RIGHT1-Pad6)") (class "Default")
      (node (ref "COB_RIGHT1") (pin "6") (pintype "input"))
    )
    (net (code "153") (name "unconnected-(COB_RIGHT2-Pad17)") (class "Default")
      (node (ref "COB_RIGHT2") (pin "17") (pintype "input"))
    )
    (net (code "154") (name "unconnected-(COB_RIGHT2-Pad19)") (class "Default")
      (node (ref "COB_RIGHT2") (pin "19") (pintype "input"))
    )
    (net (code "155") (name "unconnected-(COB_RIGHT2-Pad20)") (class "Default")
      (node (ref "COB_RIGHT2") (pin "20") (pintype "input"))
    )
    (net (code "156") (name "unconnected-(COB_RIGHT2-Pad21)") (class "Default")
      (node (ref "COB_RIGHT2") (pin "21") (pintype "input"))
    )
    (net (code "157") (name "unconnected-(COB_RIGHT2-Pad29)") (class "Default")
      (node (ref "COB_RIGHT2") (pin "29") (pintype "input"))
    )
    (net (code "158") (name "unconnected-(COB_TOP1-Pad1)") (class "Default")
      (node (ref "COB_TOP1") (pin "1") (pintype "input"))
    )
    (net (code "159") (name "unconnected-(COB_TOP1-Pad2)") (class "Default")
      (node (ref "COB_TOP1") (pin "2") (pintype "input"))
    )
    (net (code "160") (name "unconnected-(COB_TOP1-Pad3)") (class "Default")
      (node (ref "COB_TOP1") (pin "3") (pintype "input"))
    )
    (net (code "161") (name "unconnected-(COB_TOP1-Pad5)") (class "Default")
      (node (ref "COB_TOP1") (pin "5") (pintype "input"))
    )
    (net (code "162") (name "unconnected-(COB_TOP1-Pad6)") (class "Default")
      (node (ref "COB_TOP1") (pin "6") (pintype "input"))
    )
    (net (code "163") (name "unconnected-(COB_TOP1-Pad7)") (class "Default")
      (node (ref "COB_TOP1") (pin "7") (pintype "input"))
    )
    (net (code "164") (name "unconnected-(COB_TOP1-Pad8)") (class "Default")
      (node (ref "COB_TOP1") (pin "8") (pintype "input"))
    )
    (net (code "165") (name "unconnected-(COB_TOP1-Pad10)") (class "Default")
      (node (ref "COB_TOP1") (pin "10") (pintype "input"))
    )
    (net (code "166") (name "unconnected-(COB_TOP1-Pad11)") (class "Default")
      (node (ref "COB_TOP1") (pin "11") (pintype "input"))
    )
    (net (code "167") (name "unconnected-(COB_TOP1-Pad14)") (class "Default")
      (node (ref "COB_TOP1") (pin "14") (pintype "input"))
    )
    (net (code "168") (name "unconnected-(COB_TOP1-Pad15)") (class "Default")
      (node (ref "COB_TOP1") (pin "15") (pintype "input"))
    )
    (net (code "169") (name "unconnected-(COB_TOP1-Pad16)") (class "Default")
      (node (ref "COB_TOP1") (pin "16") (pintype "input"))
    )
    (net (code "170") (name "unconnected-(COB_TOP1-Pad17)") (class "Default")
      (node (ref "COB_TOP1") (pin "17") (pintype "input"))
    )
    (net (code "171") (name "unconnected-(COB_TOP1-Pad18)") (class "Default")
      (node (ref "COB_TOP1") (pin "18") (pintype "input"))
    )
    (net (code "172") (name "unconnected-(COB_TOP1-Pad19)") (class "Default")
      (node (ref "COB_TOP1") (pin "19") (pintype "input"))
    )
    (net (code "173") (name "unconnected-(COB_TOP1-Pad20)") (class "Default")
      (node (ref "COB_TOP1") (pin "20") (pintype "input"))
    )
    (net (code "174") (name "unconnected-(COB_TOP1-Pad21)") (class "Default")
      (node (ref "COB_TOP1") (pin "21") (pintype "input"))
    )
    (net (code "175") (name "unconnected-(COB_TOP1-Pad22)") (class "Default")
      (node (ref "COB_TOP1") (pin "22") (pintype "input"))
    )
    (net (code "176") (name "unconnected-(COB_TOP1-Pad25)") (class "Default")
      (node (ref "COB_TOP1") (pin "25") (pintype "input"))
    )
    (net (code "177") (name "unconnected-(COB_TOP1-Pad26)") (class "Default")
      (node (ref "COB_TOP1") (pin "26") (pintype "input"))
    )
    (net (code "178") (name "unconnected-(COB_TOP1-Pad27)") (class "Default")
      (node (ref "COB_TOP1") (pin "27") (pintype "input"))
    )
    (net (code "179") (name "unconnected-(COB_TOP1-Pad28)") (class "Default")
      (node (ref "COB_TOP1") (pin "28") (pintype "input"))
    )
    (net (code "180") (name "unconnected-(COB_TOP1-Pad29)") (class "Default")
      (node (ref "COB_TOP1") (pin "29") (pintype "input"))
    )
    (net (code "181") (name "unconnected-(COB_TOP1-Pad30)") (class "Default")
      (node (ref "COB_TOP1") (pin "30") (pintype "input"))
    )
    (net (code "182") (name "unconnected-(COB_TOP1-Pad31)") (class "Default")
      (node (ref "COB_TOP1") (pin "31") (pintype "input"))
    )
    (net (code "183") (name "unconnected-(COB_TOP1-Pad32)") (class "Default")
      (node (ref "COB_TOP1") (pin "32") (pintype "input"))
    )
    (net (code "184") (name "unconnected-(COB_TOP2-Pad1)") (class "Default")
      (node (ref "COB_TOP2") (pin "1") (pintype "input"))
    )
    (net (code "185") (name "unconnected-(COB_TOP2-Pad5)") (class "Default")
      (node (ref "COB_TOP2") (pin "5") (pintype "input"))
    )
    (net (code "186") (name "unconnected-(COB_TOP2-Pad6)") (class "Default")
      (node (ref "COB_TOP2") (pin "6") (pintype "input"))
    )
    (net (code "187") (name "unconnected-(COB_TOP2-Pad7)") (class "Default")
      (node (ref "COB_TOP2") (pin "7") (pintype "input"))
    )
    (net (code "188") (name "unconnected-(COB_TOP2-Pad8)") (class "Default")
      (node (ref "COB_TOP2") (pin "8") (pintype "input"))
    )
    (net (code "189") (name "unconnected-(COB_TOP2-Pad9)") (class "Default")
      (node (ref "COB_TOP2") (pin "9") (pintype "input"))
    )
    (net (code "190") (name "unconnected-(COB_TOP2-Pad10)") (class "Default")
      (node (ref "COB_TOP2") (pin "10") (pintype "input"))
    )
    (net (code "191") (name "unconnected-(COB_TOP2-Pad11)") (class "Default")
      (node (ref "COB_TOP2") (pin "11") (pintype "input"))
    )
    (net (code "192") (name "unconnected-(COB_TOP2-Pad12)") (class "Default")
      (node (ref "COB_TOP2") (pin "12") (pintype "input"))
    )
    (net (code "193") (name "unconnected-(COB_TOP2-Pad13)") (class "Default")
      (node (ref "COB_TOP2") (pin "13") (pintype "input"))
    )
    (net (code "194") (name "unconnected-(COB_TOP2-Pad14)") (class "Default")
      (node (ref "COB_TOP2") (pin "14") (pintype "input"))
    )
    (net (code "195") (name "unconnected-(COB_TOP2-Pad15)") (class "Default")
      (node (ref "COB_TOP2") (pin "15") (pintype "input"))
    )
    (net (code "196") (name "unconnected-(COB_TOP2-Pad16)") (class "Default")
      (node (ref "COB_TOP2") (pin "16") (pintype "input"))
    )
    (net (code "197") (name "unconnected-(COB_TOP2-Pad17)") (class "Default")
      (node (ref "COB_TOP2") (pin "17") (pintype "input"))
    )
    (net (code "198") (name "unconnected-(COB_TOP2-Pad20)") (class "Default")
      (node (ref "COB_TOP2") (pin "20") (pintype "input"))
    )
    (net (code "199") (name "unconnected-(COB_TOP2-Pad21)") (class "Default")
      (node (ref "COB_TOP2") (pin "21") (pintype "input"))
    )
    (net (code "200") (name "unconnected-(COB_TOP2-Pad22)") (class "Default")
      (node (ref "COB_TOP2") (pin "22") (pintype "input"))
    )
    (net (code "201") (name "unconnected-(COB_TOP2-Pad23)") (class "Default")
      (node (ref "COB_TOP2") (pin "23") (pintype "input"))
    )
    (net (code "202") (name "unconnected-(COB_TOP2-Pad24)") (class "Default")
      (node (ref "COB_TOP2") (pin "24") (pintype "input"))
    )
    (net (code "203") (name "unconnected-(COB_TOP2-Pad25)") (class "Default")
      (node (ref "COB_TOP2") (pin "25") (pintype "input"))
    )
    (net (code "204") (name "unconnected-(COB_TOP2-Pad26)") (class "Default")
      (node (ref "COB_TOP2") (pin "26") (pintype "input"))
    )
    (net (code "205") (name "unconnected-(COB_TOP2-Pad27)") (class "Default")
      (node (ref "COB_TOP2") (pin "27") (pintype "input"))
    )
    (net (code "206") (name "unconnected-(COB_TOP2-Pad28)") (class "Default")
      (node (ref "COB_TOP2") (pin "28") (pintype "input"))
    )
    (net (code "207") (name "unconnected-(COB_TOP2-Pad31)") (class "Default")
      (node (ref "COB_TOP2") (pin "31") (pintype "input"))
    )
    (net (code "208") (name "unconnected-(COB_TOP2-Pad32)") (class "Default")
      (node (ref "COB_TOP2") (pin "32") (pintype "input"))
    )
  )
)
